# ir_remote_smd.net
KiCad netlist of a schematic drawn in EAGLE
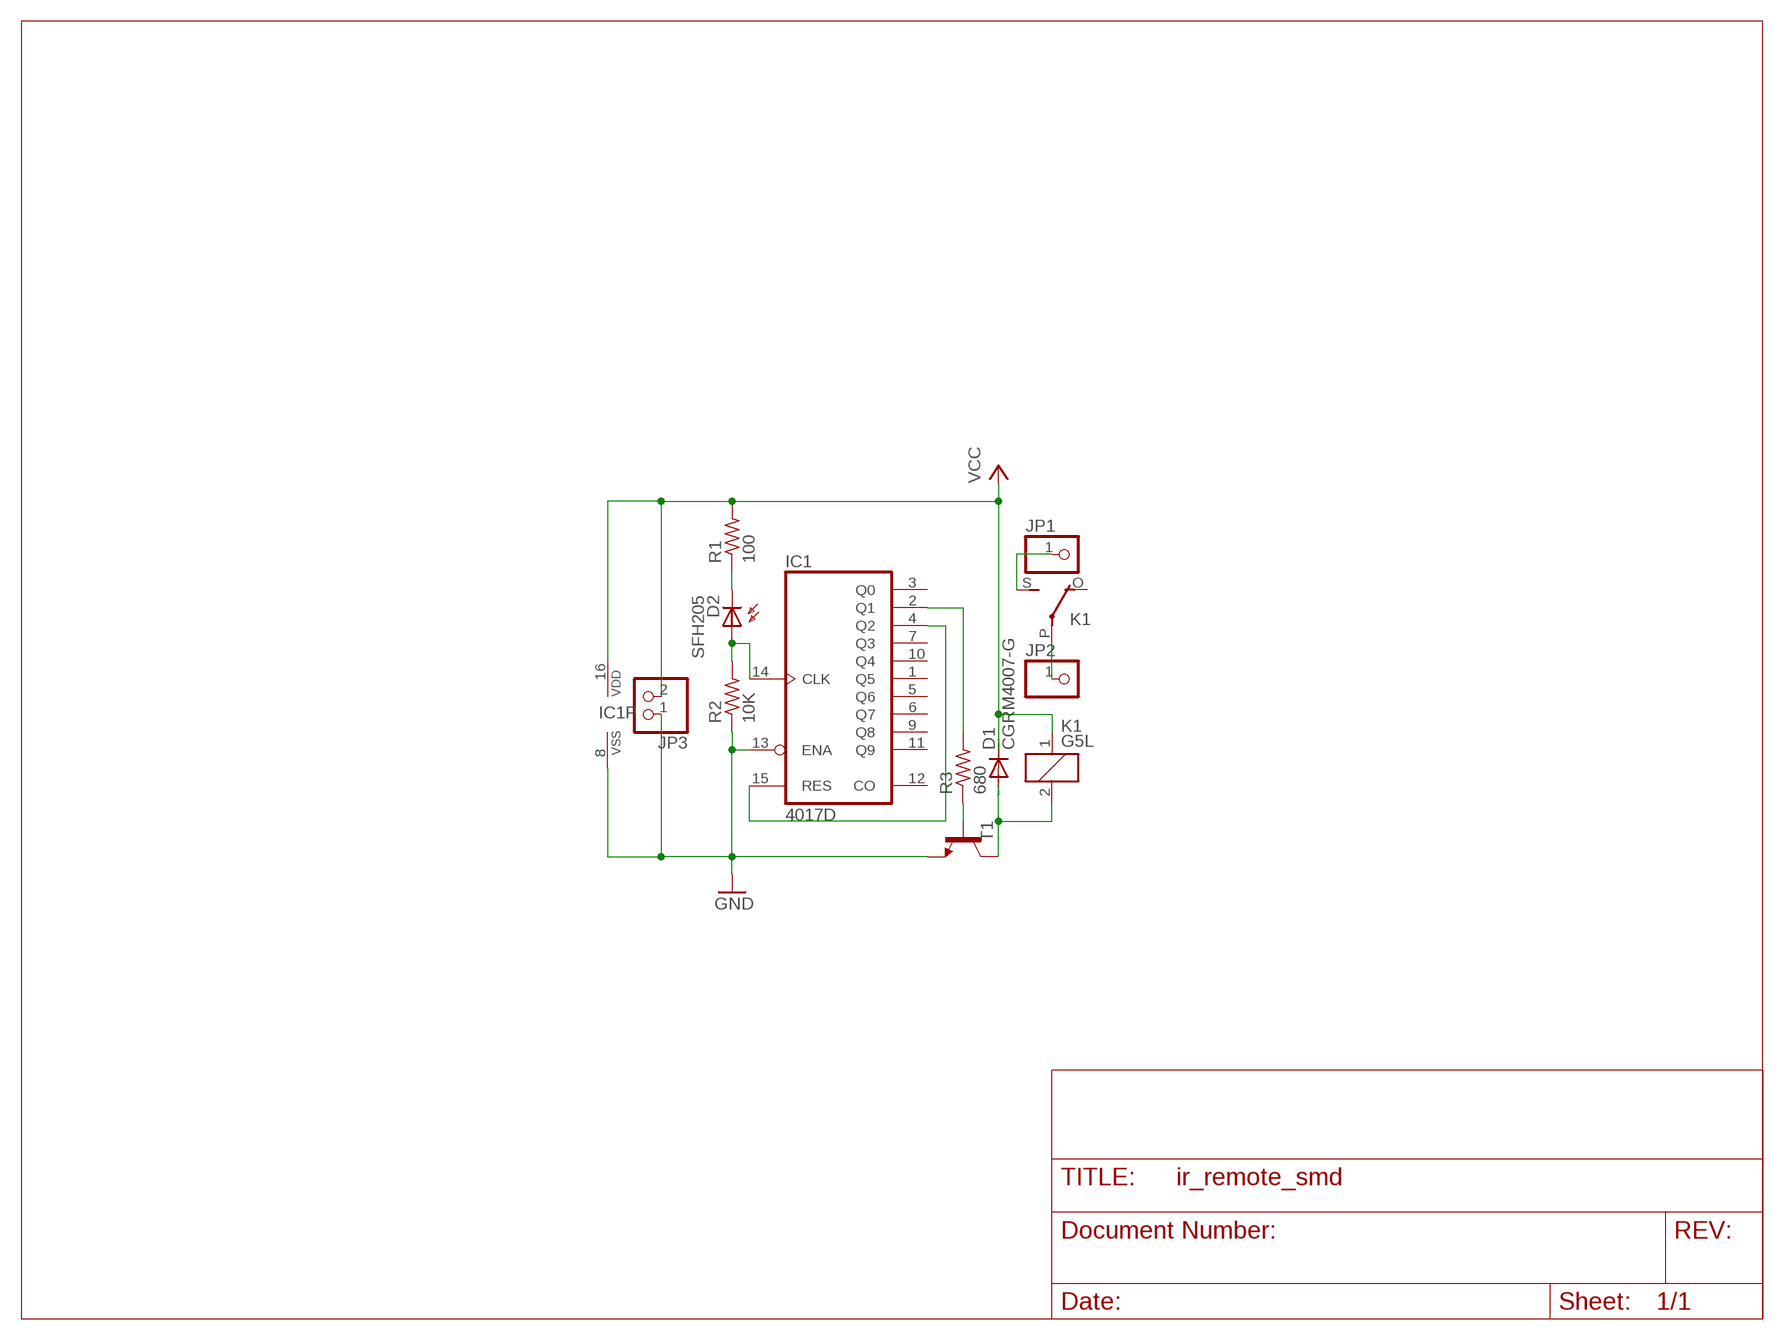
[diagram p0: schematic, sheet 1]

(export (version "E")
  (design (tool "Eeschema 10.0.6"))
  (components
    (comp (ref "D1")
      (value "CGRM4007-G")
      (footprint "eagle-import:SOD-123_MINI-SMA")
      (libsource (lib "eagle-import") (part "CGRM400-G7"))
    )
    (comp (ref "D2")
      (value "SFH205")
      (footprint "eagle-import:SFH205")
      (libsource (lib "eagle-import") (part "SFH205"))
    )
    (comp (ref "IC1")
      (value "4017D")
      (footprint "eagle-import:SO16")
      (libsource (lib "eagle-import") (part "4017D"))
    )
    (comp (ref "JP1")
      (value "PINHD-1X1")
      (footprint "eagle-import:1X01")
      (libsource (lib "eagle-import") (part "PINHD-1X1"))
    )
    (comp (ref "JP2")
      (value "PINHD-1X1")
      (footprint "eagle-import:1X01")
      (libsource (lib "eagle-import") (part "PINHD-1X1"))
    )
    (comp (ref "JP3")
      (value "PINHD-1X2")
      (footprint "eagle-import:1X02")
      (libsource (lib "eagle-import") (part "PINHD-1X2"))
    )
    (comp (ref "K1")
      (value "G5L")
      (footprint "eagle-import:G5LE")
      (libsource (lib "eagle-import") (part "G5L"))
    )
    (comp (ref "R1")
      (value "100")
      (footprint "eagle-import:R0603")
      (libsource (lib "eagle-import") (part "R-US_R0603"))
    )
    (comp (ref "R2")
      (value "10K")
      (footprint "eagle-import:R0603")
      (libsource (lib "eagle-import") (part "R-US_R0603"))
    )
    (comp (ref "R3")
      (value "680")
      (footprint "eagle-import:R0603")
      (libsource (lib "eagle-import") (part "R-US_R0603"))
    )
    (comp (ref "T1")
      (value "MMBT2222ALT1-NPN-SOT23-BEC")
      (footprint "eagle-import:SOT23-BEC")
      (libsource (lib "eagle-import") (part "-NPN-SOT23-BECMMBT2222ALT1"))
    )
  )
  (nets
    (net (code "1") (name "GND") (class "Default")
      (node (ref "IC1") (pin "13") (pinfunction "ENA_13") (pintype "input"))
      (node (ref "IC1") (pin "8") (pinfunction "VSS_8") (pintype "power_in"))
      (node (ref "JP3") (pin "1") (pinfunction "1_1") (pintype "passive"))
      (node (ref "R2") (pin "1") (pinfunction "1_1") (pintype "passive"))
      (node (ref "T1") (pin "E") (pinfunction "E_E") (pintype "passive"))
    )
    (net (code "2") (name "Net-(D1-PadA)") (class "Default")
      (node (ref "D1") (pin "A") (pinfunction "A_A") (pintype "passive"))
      (node (ref "K1") (pin "2") (pinfunction "2_2") (pintype "passive"))
      (node (ref "T1") (pin "C") (pinfunction "C_C") (pintype "passive"))
    )
    (net (code "3") (name "Net-(D2-C)") (class "Default")
      (node (ref "D2") (pin "K") (pinfunction "C_K") (pintype "passive"))
      (node (ref "R1") (pin "1") (pinfunction "1_1") (pintype "passive"))
    )
    (net (code "4") (name "Net-(IC1A-CLK)") (class "Default")
      (node (ref "D2") (pin "A") (pinfunction "A_A") (pintype "passive"))
      (node (ref "IC1") (pin "14") (pinfunction "CLK_14") (pintype "input"))
      (node (ref "R2") (pin "2") (pinfunction "2_2") (pintype "passive"))
    )
    (net (code "5") (name "Net-(IC1A-Q1)") (class "Default")
      (node (ref "IC1") (pin "2") (pinfunction "Q1_2") (pintype "output"))
      (node (ref "R3") (pin "2") (pinfunction "2_2") (pintype "passive"))
    )
    (net (code "6") (name "Net-(IC1A-Q2)") (class "Default")
      (node (ref "IC1") (pin "15") (pinfunction "RES_15") (pintype "input"))
      (node (ref "IC1") (pin "4") (pinfunction "Q2_4") (pintype "output"))
    )
    (net (code "7") (name "Net-(JP1-Pad1)") (class "Default")
      (node (ref "JP1") (pin "1") (pinfunction "1_1") (pintype "passive"))
      (node (ref "K1") (pin "S") (pinfunction "S_S") (pintype "passive"))
    )
    (net (code "8") (name "Net-(JP2-Pad1)") (class "Default")
      (node (ref "JP2") (pin "1") (pinfunction "1_1") (pintype "passive"))
      (node (ref "K1") (pin "P") (pinfunction "P_P") (pintype "passive"))
    )
    (net (code "9") (name "Net-(R3-Pad1)") (class "Default")
      (node (ref "R3") (pin "1") (pinfunction "1_1") (pintype "passive"))
      (node (ref "T1") (pin "B") (pinfunction "B_B") (pintype "passive"))
    )
    (net (code "10") (name "VCC") (class "Default")
      (node (ref "D1") (pin "C") (pinfunction "C_C") (pintype "passive"))
      (node (ref "IC1") (pin "16") (pinfunction "VDD_16") (pintype "power_in"))
      (node (ref "JP3") (pin "2") (pinfunction "2_2") (pintype "passive"))
      (node (ref "K1") (pin "1") (pinfunction "1_1") (pintype "passive"))
      (node (ref "R1") (pin "2") (pinfunction "2_2") (pintype "passive"))
    )
    (net (code "11") (name "unconnected-(IC1A-CO-Pad12)") (class "Default")
      (node (ref "IC1") (pin "12") (pinfunction "CO_12") (pintype "output"))
    )
    (net (code "12") (name "unconnected-(IC1A-Q0-Pad3)") (class "Default")
      (node (ref "IC1") (pin "3") (pinfunction "Q0_3") (pintype "output"))
    )
    (net (code "13") (name "unconnected-(IC1A-Q3-Pad7)") (class "Default")
      (node (ref "IC1") (pin "7") (pinfunction "Q3_7") (pintype "output"))
    )
    (net (code "14") (name "unconnected-(IC1A-Q4-Pad10)") (class "Default")
      (node (ref "IC1") (pin "10") (pinfunction "Q4_10") (pintype "output"))
    )
    (net (code "15") (name "unconnected-(IC1A-Q5-Pad1)") (class "Default")
      (node (ref "IC1") (pin "1") (pinfunction "Q5_1") (pintype "output"))
    )
    (net (code "16") (name "unconnected-(IC1A-Q6-Pad5)") (class "Default")
      (node (ref "IC1") (pin "5") (pinfunction "Q6_5") (pintype "output"))
    )
    (net (code "17") (name "unconnected-(IC1A-Q7-Pad6)") (class "Default")
      (node (ref "IC1") (pin "6") (pinfunction "Q7_6") (pintype "output"))
    )
    (net (code "18") (name "unconnected-(IC1A-Q8-Pad9)") (class "Default")
      (node (ref "IC1") (pin "9") (pinfunction "Q8_9") (pintype "output"))
    )
    (net (code "19") (name "unconnected-(IC1A-Q9-Pad11)") (class "Default")
      (node (ref "IC1") (pin "11") (pinfunction "Q9_11") (pintype "output"))
    )
    (net (code "20") (name "unconnected-(K1-PadO)") (class "Default")
      (node (ref "K1") (pin "O") (pinfunction "O_O") (pintype "passive"))
    )
  )
)
